# Acoustics_ADC.net
KiCad netlist of a schematic drawn in Altium Designer
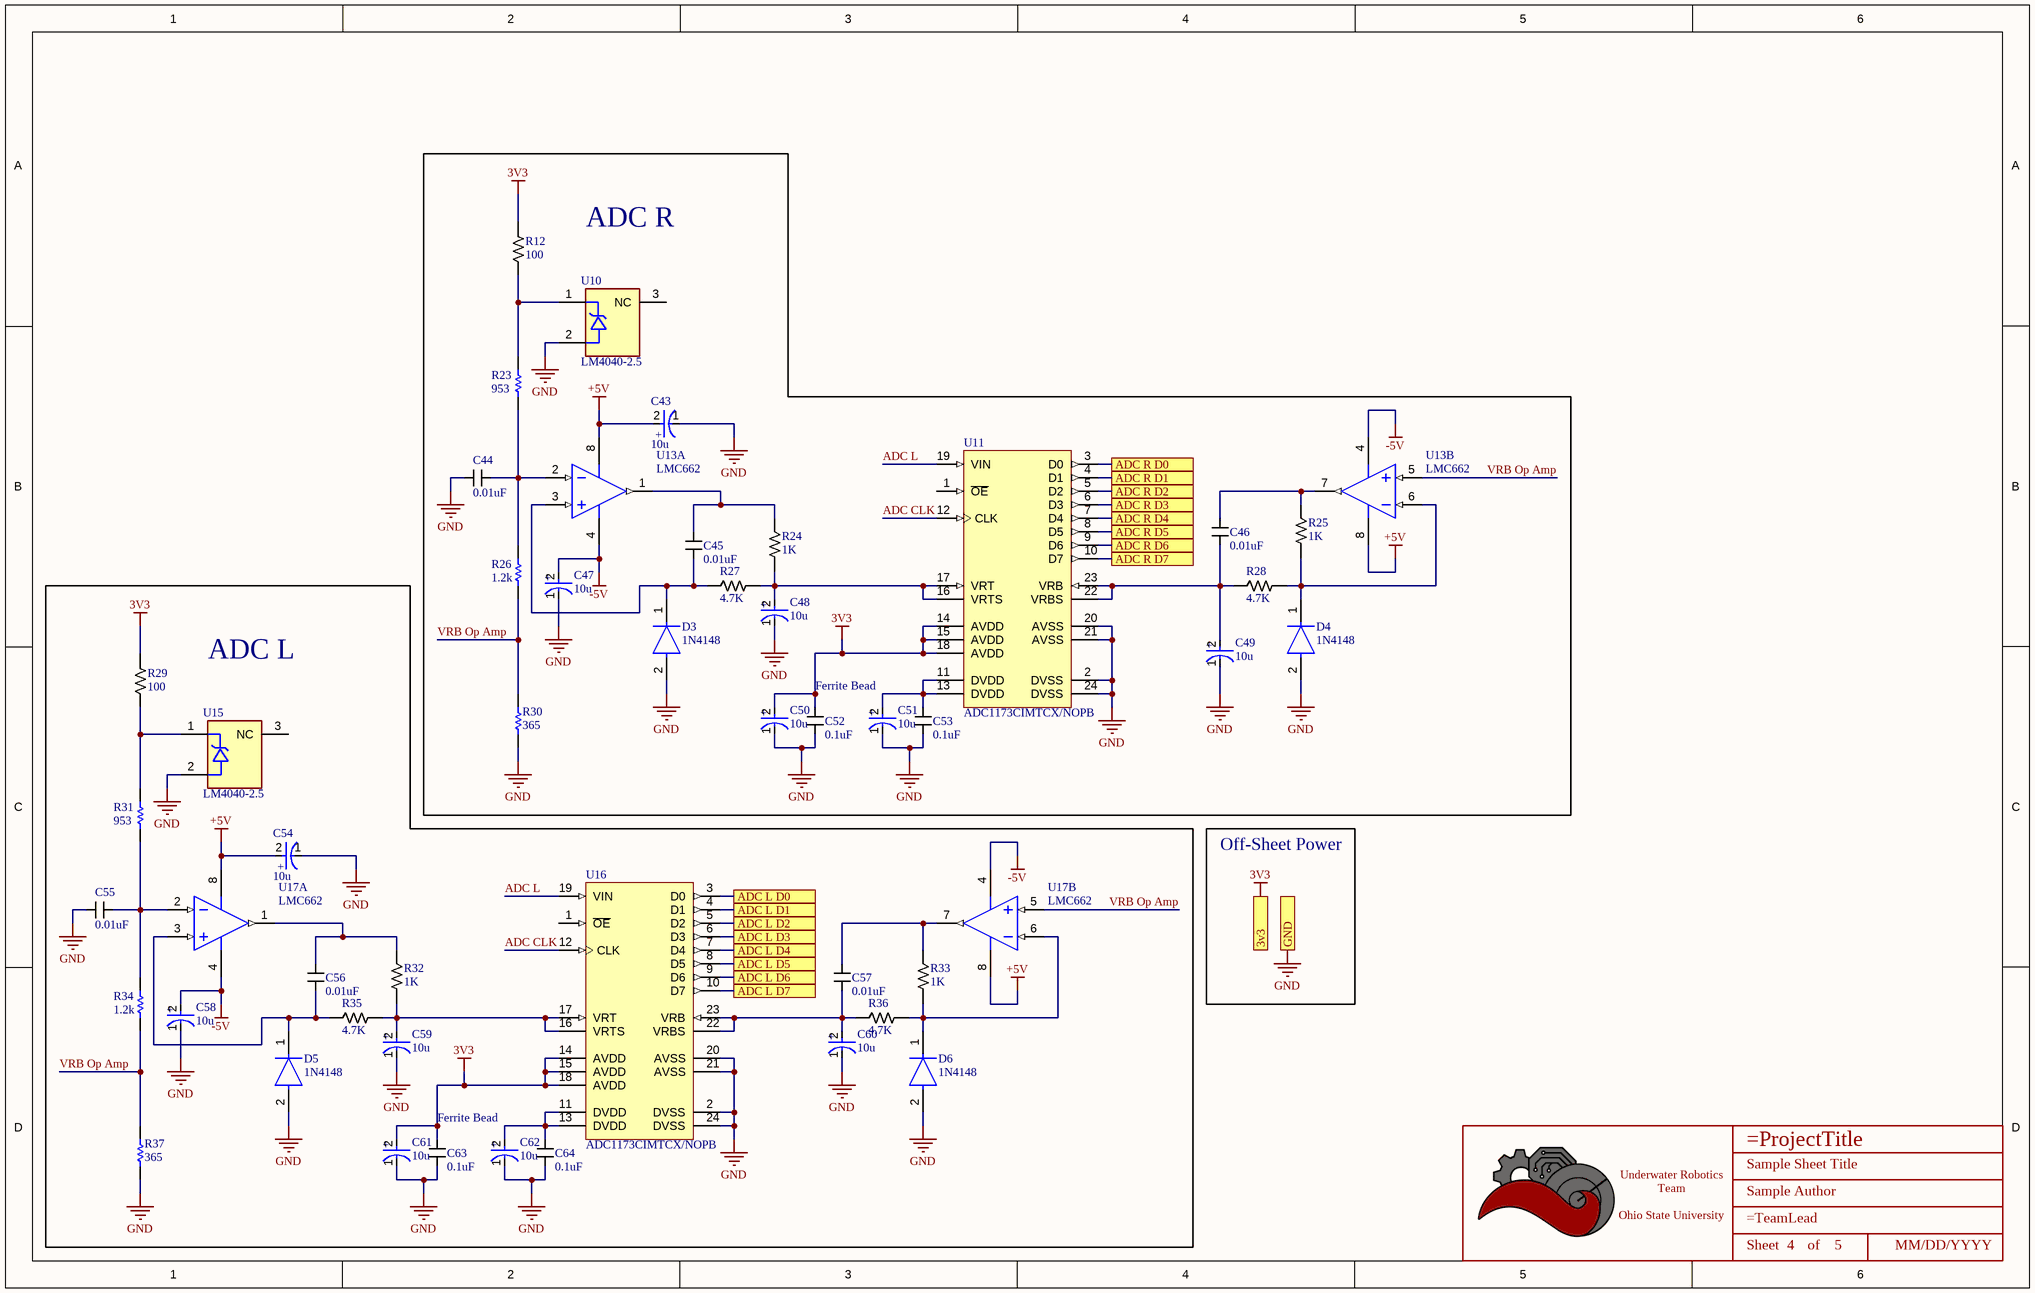
[diagram p0: [Acoustics] ADC.SchDoc]

(export (version "E")
  (design (tool "Eeschema 10.0.6"))
  (components
    (comp (ref "*")
      (value "Title_Block")
      (footprint "LOGO")
      (description "UWRT Schematic Title Block Template\r\n\r\nCreated June 2021, Dylan Trainor")
      (libsource (lib "UWRT") (part "Title_Block"))
    )
    (comp (ref "C43")
      (value "10u")
      (footprint "FP-TCJB-MFG")
      (description "10uF 25V  ±20% 90mΩ 1210  SMD Polymer Capacitor")
      (libsource (lib "Altium Content Vault") (part "a00bbbee19879c290e62620ae7e47b1"))
    )
    (comp (ref "C44")
      (value "0.01uF")
      (footprint "CAPACITOR_0603")
      (description "10000 pF ±10% 50V Ceramic Capacitor X7R 0603 (1608 Metric)")
      (fields
        (field (name "TOLERANCE") "+/- 10%")
        (field (name "VOLTAGE") "6.3V")
        (field (name "MADE BY") "Flip B")
      )
      (libsource (lib "Capacitors") (part "CAPACITOR_0.01uF_0603_50V"))
    )
    (comp (ref "C45")
      (value "0.01uF")
      (footprint "CAPACITOR_0603")
      (description "10000 pF ±10% 50V Ceramic Capacitor X7R 0603 (1608 Metric)")
      (fields
        (field (name "TOLERANCE") "+/- 10%")
        (field (name "VOLTAGE") "6.3V")
        (field (name "MADE BY") "Flip B")
      )
      (libsource (lib "Capacitors") (part "CAPACITOR_0.01uF_0603_50V"))
    )
    (comp (ref "C46")
      (value "0.01uF")
      (footprint "CAPACITOR_0603")
      (description "10000 pF ±10% 50V Ceramic Capacitor X7R 0603 (1608 Metric)")
      (fields
        (field (name "TOLERANCE") "+/- 10%")
        (field (name "VOLTAGE") "6.3V")
        (field (name "MADE BY") "Flip B")
      )
      (libsource (lib "Capacitors") (part "CAPACITOR_0.01uF_0603_50V"))
    )
    (comp (ref "C47")
      (value "10u")
      (footprint "FP-TCJB-MFG")
      (description "10uF 25V  ±20% 90mΩ 1210  SMD Polymer Capacitor")
      (libsource (lib "Altium Content Vault") (part "a00bbbee19879c290e62620ae7e47b1"))
    )
    (comp (ref "C48")
      (value "10u")
      (footprint "FP-TCJB-MFG")
      (description "10uF 25V  ±20% 90mΩ 1210  SMD Polymer Capacitor")
      (libsource (lib "Altium Content Vault") (part "a00bbbee19879c290e62620ae7e47b1"))
    )
    (comp (ref "C49")
      (value "10u")
      (footprint "FP-TCJB-MFG")
      (description "10uF 25V  ±20% 90mΩ 1210  SMD Polymer Capacitor")
      (libsource (lib "Altium Content Vault") (part "a00bbbee19879c290e62620ae7e47b1"))
    )
    (comp (ref "C50")
      (value "10u")
      (footprint "FP-TCJB-MFG")
      (description "10uF 25V  ±20% 90mΩ 1210  SMD Polymer Capacitor")
      (libsource (lib "Altium Content Vault") (part "a00bbbee19879c290e62620ae7e47b1"))
    )
    (comp (ref "C51")
      (value "10u")
      (footprint "FP-TCJB-MFG")
      (description "10uF 25V  ±20% 90mΩ 1210  SMD Polymer Capacitor")
      (libsource (lib "Altium Content Vault") (part "a00bbbee19879c290e62620ae7e47b1"))
    )
    (comp (ref "C52")
      (value "0.1uF")
      (footprint "CAPACITOR_0603")
      (description "Cap 100nF 6.3V +/-10%\r\nCeramic 0603")
      (fields
        (field (name "TOLERANCE") "+/- 10%")
        (field (name "VOLTAGE") "6.3V")
        (field (name "MADE BY") "Flip B")
      )
      (libsource (lib "Capacitors") (part "CAPACITOR_0.1uF_0603"))
    )
    (comp (ref "C53")
      (value "0.1uF")
      (footprint "CAPACITOR_0603")
      (description "Cap 100nF 6.3V +/-10%\r\nCeramic 0603")
      (fields
        (field (name "TOLERANCE") "+/- 10%")
        (field (name "VOLTAGE") "6.3V")
        (field (name "MADE BY") "Flip B")
      )
      (libsource (lib "Capacitors") (part "CAPACITOR_0.1uF_0603"))
    )
    (comp (ref "C54")
      (value "10u")
      (footprint "FP-TCJB-MFG")
      (description "10uF 25V  ±20% 90mΩ 1210  SMD Polymer Capacitor")
      (libsource (lib "Altium Content Vault") (part "a00bbbee19879c290e62620ae7e47b1"))
    )
    (comp (ref "C55")
      (value "0.01uF")
      (footprint "CAPACITOR_0603")
      (description "10000 pF ±10% 50V Ceramic Capacitor X7R 0603 (1608 Metric)")
      (fields
        (field (name "TOLERANCE") "+/- 10%")
        (field (name "VOLTAGE") "6.3V")
        (field (name "MADE BY") "Flip B")
      )
      (libsource (lib "Capacitors") (part "CAPACITOR_0.01uF_0603_50V"))
    )
    (comp (ref "C56")
      (value "0.01uF")
      (footprint "CAPACITOR_0603")
      (description "10000 pF ±10% 50V Ceramic Capacitor X7R 0603 (1608 Metric)")
      (fields
        (field (name "TOLERANCE") "+/- 10%")
        (field (name "VOLTAGE") "6.3V")
        (field (name "MADE BY") "Flip B")
      )
      (libsource (lib "Capacitors") (part "CAPACITOR_0.01uF_0603_50V"))
    )
    (comp (ref "C57")
      (value "0.01uF")
      (footprint "CAPACITOR_0603")
      (description "10000 pF ±10% 50V Ceramic Capacitor X7R 0603 (1608 Metric)")
      (fields
        (field (name "TOLERANCE") "+/- 10%")
        (field (name "VOLTAGE") "6.3V")
        (field (name "MADE BY") "Flip B")
      )
      (libsource (lib "Capacitors") (part "CAPACITOR_0.01uF_0603_50V"))
    )
    (comp (ref "C58")
      (value "10u")
      (footprint "FP-TCJB-MFG")
      (description "10uF 25V  ±20% 90mΩ 1210  SMD Polymer Capacitor")
      (libsource (lib "Altium Content Vault") (part "a00bbbee19879c290e62620ae7e47b1"))
    )
    (comp (ref "C59")
      (value "10u")
      (footprint "FP-TCJB-MFG")
      (description "10uF 25V  ±20% 90mΩ 1210  SMD Polymer Capacitor")
      (libsource (lib "Altium Content Vault") (part "a00bbbee19879c290e62620ae7e47b1"))
    )
    (comp (ref "C60")
      (value "10u")
      (footprint "FP-TCJB-MFG")
      (description "10uF 25V  ±20% 90mΩ 1210  SMD Polymer Capacitor")
      (libsource (lib "Altium Content Vault") (part "a00bbbee19879c290e62620ae7e47b1"))
    )
    (comp (ref "C61")
      (value "10u")
      (footprint "FP-TCJB-MFG")
      (description "10uF 25V  ±20% 90mΩ 1210  SMD Polymer Capacitor")
      (libsource (lib "Altium Content Vault") (part "a00bbbee19879c290e62620ae7e47b1"))
    )
    (comp (ref "C62")
      (value "10u")
      (footprint "FP-TCJB-MFG")
      (description "10uF 25V  ±20% 90mΩ 1210  SMD Polymer Capacitor")
      (libsource (lib "Altium Content Vault") (part "a00bbbee19879c290e62620ae7e47b1"))
    )
    (comp (ref "C63")
      (value "0.1uF")
      (footprint "CAPACITOR_0603")
      (description "Cap 100nF 6.3V +/-10%\r\nCeramic 0603")
      (fields
        (field (name "TOLERANCE") "+/- 10%")
        (field (name "VOLTAGE") "6.3V")
        (field (name "MADE BY") "Flip B")
      )
      (libsource (lib "Capacitors") (part "CAPACITOR_0.1uF_0603"))
    )
    (comp (ref "C64")
      (value "0.1uF")
      (footprint "CAPACITOR_0603")
      (description "Cap 100nF 6.3V +/-10%\r\nCeramic 0603")
      (fields
        (field (name "TOLERANCE") "+/- 10%")
        (field (name "VOLTAGE") "6.3V")
        (field (name "MADE BY") "Flip B")
      )
      (libsource (lib "Capacitors") (part "CAPACITOR_0.1uF_0603"))
    )
    (comp (ref "D3")
      (value "1N4148")
      (footprint "FP-017AG-MFG")
      (description "DIODE GEN PURP 100V 200MA DO35")
      (fields (field (name "VOLTAGE") "100V"))
      (libsource (lib "Altium Content Vault") (part "d7152d700b627762746794eb795d46e"))
    )
    (comp (ref "D4")
      (value "1N4148")
      (footprint "FP-017AG-MFG")
      (description "DIODE GEN PURP 100V 200MA DO35")
      (fields (field (name "VOLTAGE") "100V"))
      (libsource (lib "Altium Content Vault") (part "d7152d700b627762746794eb795d46e"))
    )
    (comp (ref "D5")
      (value "1N4148")
      (footprint "FP-017AG-MFG")
      (description "DIODE GEN PURP 100V 200MA DO35")
      (fields (field (name "VOLTAGE") "100V"))
      (libsource (lib "Altium Content Vault") (part "d7152d700b627762746794eb795d46e"))
    )
    (comp (ref "D6")
      (value "1N4148")
      (footprint "FP-017AG-MFG")
      (description "DIODE GEN PURP 100V 200MA DO35")
      (fields (field (name "VOLTAGE") "100V"))
      (libsource (lib "Altium Content Vault") (part "d7152d700b627762746794eb795d46e"))
    )
    (comp (ref "R12")
      (value "100 Ohm 5% 1/16W")
      (footprint "RESISTOR_0402")
      (description "RES 100 OHM 5% 1/16W 0402")
      (fields
        (field (name "TOLERANCE") "+/- 5%")
        (field (name "VALUE  (OHMS)") "100")
        (field (name "MADE BY") "Flip B")
      )
      (libsource (lib "Resistors") (part "RESISTOR_100_0402"))
    )
    (comp (ref "R23")
      (value "953")
      (footprint "RESC1005X40X25ML05T05")
      (fields (field (name "PART NUMBER") "ERJ-2RKF9530X") (field (name "MANUFACTURER") "Panasonic"))
      (libsource (lib "Altium Content Vault") (part "RES"))
    )
    (comp (ref "R24")
      (value "1k Ohm 1% 1/16W")
      (footprint "RESISTOR_0402")
      (description "RES 1k OHM 1% 1/16W 0402")
      (fields
        (field (name "TOLERANCE") "+/- 1%")
        (field (name "VALUE  (OHMS)") "1K")
        (field (name "MADE BY") "Robert Pafford")
      )
      (libsource (lib "Resistors") (part "RESISTOR_1K_0402"))
    )
    (comp (ref "R25")
      (value "1k Ohm 1% 1/16W")
      (footprint "RESISTOR_0402")
      (description "RES 1k OHM 1% 1/16W 0402")
      (fields
        (field (name "TOLERANCE") "+/- 1%")
        (field (name "VALUE  (OHMS)") "1K")
        (field (name "MADE BY") "Robert Pafford")
      )
      (libsource (lib "Resistors") (part "RESISTOR_1K_0402"))
    )
    (comp (ref "R26")
      (value "1.2k")
      (footprint "RESC1005X40X25NL05T10")
      (fields (field (name "PART NUMBER") "RC0402JR-071K2L") (field (name "MANUFACTURER") "Yageo / Phycomp"))
      (libsource (lib "Altium Content Vault") (part "RES"))
    )
    (comp (ref "R27")
      (value "4.7k Ohm 1% 1/16W")
      (footprint "RESISTOR_0402")
      (description "RES 4.7k OHM 1% 1/16W 0402")
      (fields
        (field (name "TOLERANCE") "+/- 1%")
        (field (name "VALUE  (OHMS)") "4.7K")
        (field (name "MADE BY") "Robert Pafford")
      )
      (libsource (lib "Resistors") (part "RESISTOR_4.7K_0402"))
    )
    (comp (ref "R28")
      (value "4.7k Ohm 1% 1/16W")
      (footprint "RESISTOR_0402")
      (description "RES 4.7k OHM 1% 1/16W 0402")
      (fields
        (field (name "TOLERANCE") "+/- 1%")
        (field (name "VALUE  (OHMS)") "4.7K")
        (field (name "MADE BY") "Robert Pafford")
      )
      (libsource (lib "Resistors") (part "RESISTOR_4.7K_0402"))
    )
    (comp (ref "R29")
      (value "100 Ohm 5% 1/16W")
      (footprint "RESISTOR_0402")
      (description "RES 100 OHM 5% 1/16W 0402")
      (fields
        (field (name "TOLERANCE") "+/- 5%")
        (field (name "VALUE  (OHMS)") "100")
        (field (name "MADE BY") "Flip B")
      )
      (libsource (lib "Resistors") (part "RESISTOR_100_0402"))
    )
    (comp (ref "R30")
      (value "365")
      (footprint "RESC1005X40X25ML05T05")
      (fields (field (name "PART NUMBER") "ERJ-2RKF3650X") (field (name "MANUFACTURER") "Panasonic"))
      (libsource (lib "Altium Content Vault") (part "RES"))
    )
    (comp (ref "R31")
      (value "953")
      (footprint "RESC1005X40X25ML05T05")
      (fields (field (name "PART NUMBER") "ERJ-2RKF9530X") (field (name "MANUFACTURER") "Panasonic"))
      (libsource (lib "Altium Content Vault") (part "RES"))
    )
    (comp (ref "R32")
      (value "1k Ohm 1% 1/16W")
      (footprint "RESISTOR_0402")
      (description "RES 1k OHM 1% 1/16W 0402")
      (fields
        (field (name "TOLERANCE") "+/- 1%")
        (field (name "VALUE  (OHMS)") "1K")
        (field (name "MADE BY") "Robert Pafford")
      )
      (libsource (lib "Resistors") (part "RESISTOR_1K_0402"))
    )
    (comp (ref "R33")
      (value "1k Ohm 1% 1/16W")
      (footprint "RESISTOR_0402")
      (description "RES 1k OHM 1% 1/16W 0402")
      (fields
        (field (name "TOLERANCE") "+/- 1%")
        (field (name "VALUE  (OHMS)") "1K")
        (field (name "MADE BY") "Robert Pafford")
      )
      (libsource (lib "Resistors") (part "RESISTOR_1K_0402"))
    )
    (comp (ref "R34")
      (value "1.2k")
      (footprint "RESC1005X40X25NL05T10")
      (fields (field (name "PART NUMBER") "RC0402JR-071K2L") (field (name "MANUFACTURER") "Yageo / Phycomp"))
      (libsource (lib "Altium Content Vault") (part "RES"))
    )
    (comp (ref "R35")
      (value "4.7k Ohm 1% 1/16W")
      (footprint "RESISTOR_0402")
      (description "RES 4.7k OHM 1% 1/16W 0402")
      (fields
        (field (name "TOLERANCE") "+/- 1%")
        (field (name "VALUE  (OHMS)") "4.7K")
        (field (name "MADE BY") "Robert Pafford")
      )
      (libsource (lib "Resistors") (part "RESISTOR_4.7K_0402"))
    )
    (comp (ref "R36")
      (value "4.7k Ohm 1% 1/16W")
      (footprint "RESISTOR_0402")
      (description "RES 4.7k OHM 1% 1/16W 0402")
      (fields
        (field (name "TOLERANCE") "+/- 1%")
        (field (name "VALUE  (OHMS)") "4.7K")
        (field (name "MADE BY") "Robert Pafford")
      )
      (libsource (lib "Resistors") (part "RESISTOR_4.7K_0402"))
    )
    (comp (ref "R37")
      (value "365")
      (footprint "RESC1005X40X25ML05T05")
      (fields (field (name "PART NUMBER") "ERJ-2RKF3650X") (field (name "MANUFACTURER") "Panasonic"))
      (libsource (lib "Altium Content Vault") (part "RES"))
    )
    (comp (ref "U10")
      (value "LM4040-2.5")
      (footprint "FP-SOT23-3LD-PL-1-MFG")
      (description "IC VREF SHUNT 2.5V SOT23-3")
      (fields
        (field (name "MANUFACTURER") "Microchip")
        (field (name "MANUFACTURER PART NUMBER") "LM4040CYM3-2.5-TR")
      )
      (libsource (lib "Altium Content Vault") (part "e08089692d8b94833b83a492544ec0b"))
    )
    (comp (ref "U11")
      (value "ADC1173CIMTCX/NOPB")
      (footprint "PW0024A_L")
      (description "8-Bit, 3-Volt, 15MSPS, 33mW A/D Converter, 24-pin TSSOP, Pb-Free")
      (fields (field (name "MANUFACTURER") "Texas Instruments"))
      (libsource (lib "Altium Content Vault") (part "CON-ADC-ADC1175CIMTC"))
    )
    (comp (ref "U13")
      (value "LMC662")
      (footprint "D0008A_L")
      (description "CMOS Dual Operational Amplifier, 8-pin Narrow SOIC, Pb-Free")
      (fields (field (name "MANUFACTURER") "Texas Instruments"))
      (libsource (lib "Altium Content Vault") (part "AMP-OPA-LF353-8"))
    )
    (comp (ref "U15")
      (value "LM4040-2.5")
      (footprint "FP-SOT23-3LD-PL-1-MFG")
      (description "IC VREF SHUNT 2.5V SOT23-3")
      (fields
        (field (name "MANUFACTURER") "Microchip")
        (field (name "MANUFACTURER PART NUMBER") "LM4040CYM3-2.5-TR")
      )
      (libsource (lib "Altium Content Vault") (part "e08089692d8b94833b83a492544ec0b"))
    )
    (comp (ref "U16")
      (value "ADC1173CIMTCX/NOPB")
      (footprint "PW0024A_L")
      (description "8-Bit, 3-Volt, 15MSPS, 33mW A/D Converter, 24-pin TSSOP, Pb-Free")
      (fields (field (name "MANUFACTURER") "Texas Instruments"))
      (libsource (lib "Altium Content Vault") (part "CON-ADC-ADC1175CIMTC"))
    )
    (comp (ref "U17")
      (value "LMC662")
      (footprint "D0008A_L")
      (description "CMOS Dual Operational Amplifier, 8-pin Narrow SOIC, Pb-Free")
      (fields (field (name "MANUFACTURER") "Texas Instruments"))
      (libsource (lib "Altium Content Vault") (part "AMP-OPA-LF353-8"))
    )
  )
  (nets
    (net (code "1") (name "+5V") (class "Default")
      (node (ref "C43") (pin "2") (pinfunction "A_2") (pintype "passive"))
      (node (ref "C54") (pin "2") (pinfunction "A_2") (pintype "passive"))
      (node (ref "U13") (pin "8") (pinfunction "V+_8") (pintype "power_in"))
      (node (ref "U17") (pin "8") (pinfunction "V+_8") (pintype "power_in"))
    )
    (net (code "2") (name "-5V") (class "Default")
      (node (ref "C47") (pin "2") (pinfunction "A_2") (pintype "passive"))
      (node (ref "C58") (pin "2") (pinfunction "A_2") (pintype "passive"))
      (node (ref "U13") (pin "4") (pinfunction "V-_4") (pintype "power_in"))
      (node (ref "U17") (pin "4") (pinfunction "V-_4") (pintype "power_in"))
    )
    (net (code "3") (name "/ADC CLK") (class "Default")
      (node (ref "U11") (pin "12") (pinfunction "CLK_12") (pintype "input"))
      (node (ref "U16") (pin "12") (pinfunction "CLK_12") (pintype "input"))
    )
    (net (code "4") (name "/ADC L") (class "Default")
      (node (ref "U11") (pin "19") (pinfunction "VIN_19") (pintype "input"))
      (node (ref "U16") (pin "19") (pinfunction "VIN_19") (pintype "input"))
    )
    (net (code "5") (name "/ADC L D0") (class "Default")
      (node (ref "U16") (pin "3") (pinfunction "D0_3") (pintype "output"))
    )
    (net (code "6") (name "/ADC L D1") (class "Default")
      (node (ref "U16") (pin "4") (pinfunction "D1_4") (pintype "output"))
    )
    (net (code "7") (name "/ADC L D2") (class "Default")
      (node (ref "U16") (pin "5") (pinfunction "D2_5") (pintype "output"))
    )
    (net (code "8") (name "/ADC L D3") (class "Default")
      (node (ref "U16") (pin "6") (pinfunction "D3_6") (pintype "output"))
    )
    (net (code "9") (name "/ADC L D4") (class "Default")
      (node (ref "U16") (pin "7") (pinfunction "D4_7") (pintype "output"))
    )
    (net (code "10") (name "/ADC L D5") (class "Default")
      (node (ref "U16") (pin "8") (pinfunction "D5_8") (pintype "output"))
    )
    (net (code "11") (name "/ADC L D6") (class "Default")
      (node (ref "U16") (pin "9") (pinfunction "D6_9") (pintype "output"))
    )
    (net (code "12") (name "/ADC L D7") (class "Default")
      (node (ref "U16") (pin "10") (pinfunction "D7_10") (pintype "output"))
    )
    (net (code "13") (name "/ADC R D0") (class "Default")
      (node (ref "U11") (pin "3") (pinfunction "D0_3") (pintype "output"))
    )
    (net (code "14") (name "/ADC R D1") (class "Default")
      (node (ref "U11") (pin "4") (pinfunction "D1_4") (pintype "output"))
    )
    (net (code "15") (name "/ADC R D2") (class "Default")
      (node (ref "U11") (pin "5") (pinfunction "D2_5") (pintype "output"))
    )
    (net (code "16") (name "/ADC R D3") (class "Default")
      (node (ref "U11") (pin "6") (pinfunction "D3_6") (pintype "output"))
    )
    (net (code "17") (name "/ADC R D4") (class "Default")
      (node (ref "U11") (pin "7") (pinfunction "D4_7") (pintype "output"))
    )
    (net (code "18") (name "/ADC R D5") (class "Default")
      (node (ref "U11") (pin "8") (pinfunction "D5_8") (pintype "output"))
    )
    (net (code "19") (name "/ADC R D6") (class "Default")
      (node (ref "U11") (pin "9") (pinfunction "D6_9") (pintype "output"))
    )
    (net (code "20") (name "/ADC R D7") (class "Default")
      (node (ref "U11") (pin "10") (pinfunction "D7_10") (pintype "output"))
    )
    (net (code "21") (name "/VRB Op Amp") (class "Default")
      (node (ref "R26") (pin "1") (pinfunction "1_1") (pintype "passive"))
      (node (ref "R30") (pin "2") (pinfunction "2_2") (pintype "passive"))
      (node (ref "R34") (pin "1") (pinfunction "1_1") (pintype "passive"))
      (node (ref "R37") (pin "2") (pinfunction "2_2") (pintype "passive"))
      (node (ref "U13") (pin "5") (pinfunction "INB+_5") (pintype "input"))
      (node (ref "U17") (pin "5") (pinfunction "INB+_5") (pintype "input"))
    )
    (net (code "22") (name "3V3") (class "Default")
      (node (ref "C50") (pin "2") (pinfunction "A_2") (pintype "passive"))
      (node (ref "C52") (pin "1") (pinfunction "1_1") (pintype "passive"))
      (node (ref "C61") (pin "2") (pinfunction "A_2") (pintype "passive"))
      (node (ref "C63") (pin "1") (pinfunction "1_1") (pintype "passive"))
      (node (ref "R12") (pin "1") (pinfunction "1_1") (pintype "passive"))
      (node (ref "R29") (pin "1") (pinfunction "1_1") (pintype "passive"))
      (node (ref "U11") (pin "14") (pinfunction "AVDD_14") (pintype "power_in"))
      (node (ref "U11") (pin "15") (pinfunction "AVDD_15") (pintype "power_in"))
      (node (ref "U11") (pin "18") (pinfunction "AVDD_18") (pintype "power_in"))
      (node (ref "U16") (pin "14") (pinfunction "AVDD_14") (pintype "power_in"))
      (node (ref "U16") (pin "15") (pinfunction "AVDD_15") (pintype "power_in"))
      (node (ref "U16") (pin "18") (pinfunction "AVDD_18") (pintype "power_in"))
    )
    (net (code "23") (name "GND") (class "Default")
      (node (ref "C43") (pin "1") (pinfunction "C_1") (pintype "passive"))
      (node (ref "C44") (pin "2") (pinfunction "2_2") (pintype "passive"))
      (node (ref "C47") (pin "1") (pinfunction "C_1") (pintype "passive"))
      (node (ref "C48") (pin "1") (pinfunction "C_1") (pintype "passive"))
      (node (ref "C49") (pin "1") (pinfunction "C_1") (pintype "passive"))
      (node (ref "C50") (pin "1") (pinfunction "C_1") (pintype "passive"))
      (node (ref "C51") (pin "1") (pinfunction "C_1") (pintype "passive"))
      (node (ref "C52") (pin "2") (pinfunction "2_2") (pintype "passive"))
      (node (ref "C53") (pin "2") (pinfunction "2_2") (pintype "passive"))
      (node (ref "C54") (pin "1") (pinfunction "C_1") (pintype "passive"))
      (node (ref "C55") (pin "2") (pinfunction "2_2") (pintype "passive"))
      (node (ref "C58") (pin "1") (pinfunction "C_1") (pintype "passive"))
      (node (ref "C59") (pin "1") (pinfunction "C_1") (pintype "passive"))
      (node (ref "C60") (pin "1") (pinfunction "C_1") (pintype "passive"))
      (node (ref "C61") (pin "1") (pinfunction "C_1") (pintype "passive"))
      (node (ref "C62") (pin "1") (pinfunction "C_1") (pintype "passive"))
      (node (ref "C63") (pin "2") (pinfunction "2_2") (pintype "passive"))
      (node (ref "C64") (pin "2") (pinfunction "2_2") (pintype "passive"))
      (node (ref "D3") (pin "2") (pinfunction "A_2") (pintype "passive"))
      (node (ref "D4") (pin "2") (pinfunction "A_2") (pintype "passive"))
      (node (ref "D5") (pin "2") (pinfunction "A_2") (pintype "passive"))
      (node (ref "D6") (pin "2") (pinfunction "A_2") (pintype "passive"))
      (node (ref "R30") (pin "1") (pinfunction "1_1") (pintype "passive"))
      (node (ref "R37") (pin "1") (pinfunction "1_1") (pintype "passive"))
      (node (ref "U10") (pin "2") (pinfunction "-_2") (pintype "passive"))
      (node (ref "U11") (pin "2") (pinfunction "DVSS_2") (pintype "power_in"))
      (node (ref "U11") (pin "20") (pinfunction "AVSS_20") (pintype "power_in"))
      (node (ref "U11") (pin "21") (pinfunction "AVSS_21") (pintype "power_in"))
      (node (ref "U11") (pin "24") (pinfunction "DVSS_24") (pintype "power_in"))
      (node (ref "U15") (pin "2") (pinfunction "-_2") (pintype "passive"))
      (node (ref "U16") (pin "2") (pinfunction "DVSS_2") (pintype "power_in"))
      (node (ref "U16") (pin "20") (pinfunction "AVSS_20") (pintype "power_in"))
      (node (ref "U16") (pin "21") (pinfunction "AVSS_21") (pintype "power_in"))
      (node (ref "U16") (pin "24") (pinfunction "DVSS_24") (pintype "power_in"))
    )
    (net (code "24") (name "Net-(C48-A)") (class "Default")
      (node (ref "C48") (pin "2") (pinfunction "A_2") (pintype "passive"))
      (node (ref "R24") (pin "1") (pinfunction "1_1") (pintype "passive"))
      (node (ref "R27") (pin "1") (pinfunction "1_1") (pintype "passive"))
      (node (ref "U11") (pin "16") (pinfunction "VRTS_16") (pintype "passive"))
      (node (ref "U11") (pin "17") (pinfunction "VRT_17") (pintype "input"))
    )
    (net (code "25") (name "Net-(C49-A)") (class "Default")
      (node (ref "C46") (pin "2") (pinfunction "2_2") (pintype "passive"))
      (node (ref "C49") (pin "2") (pinfunction "A_2") (pintype "passive"))
      (node (ref "R28") (pin "2") (pinfunction "2_2") (pintype "passive"))
      (node (ref "U11") (pin "22") (pinfunction "VRBS_22") (pintype "passive"))
      (node (ref "U11") (pin "23") (pinfunction "VRB_23") (pintype "input"))
    )
    (net (code "26") (name "Net-(C51-A)") (class "Default")
      (node (ref "C51") (pin "2") (pinfunction "A_2") (pintype "passive"))
      (node (ref "C53") (pin "1") (pinfunction "1_1") (pintype "passive"))
      (node (ref "U11") (pin "11") (pinfunction "DVDD_11") (pintype "power_in"))
      (node (ref "U11") (pin "13") (pinfunction "DVDD_13") (pintype "power_in"))
    )
    (net (code "27") (name "Net-(C59-A)") (class "Default")
      (node (ref "C59") (pin "2") (pinfunction "A_2") (pintype "passive"))
      (node (ref "R32") (pin "1") (pinfunction "1_1") (pintype "passive"))
      (node (ref "R35") (pin "1") (pinfunction "1_1") (pintype "passive"))
      (node (ref "U16") (pin "16") (pinfunction "VRTS_16") (pintype "passive"))
      (node (ref "U16") (pin "17") (pinfunction "VRT_17") (pintype "input"))
    )
    (net (code "28") (name "Net-(C60-A)") (class "Default")
      (node (ref "C57") (pin "2") (pinfunction "2_2") (pintype "passive"))
      (node (ref "C60") (pin "2") (pinfunction "A_2") (pintype "passive"))
      (node (ref "R36") (pin "2") (pinfunction "2_2") (pintype "passive"))
      (node (ref "U16") (pin "22") (pinfunction "VRBS_22") (pintype "passive"))
      (node (ref "U16") (pin "23") (pinfunction "VRB_23") (pintype "input"))
    )
    (net (code "29") (name "Net-(C62-A)") (class "Default")
      (node (ref "C62") (pin "2") (pinfunction "A_2") (pintype "passive"))
      (node (ref "C64") (pin "1") (pinfunction "1_1") (pintype "passive"))
      (node (ref "U16") (pin "11") (pinfunction "DVDD_11") (pintype "power_in"))
      (node (ref "U16") (pin "13") (pinfunction "DVDD_13") (pintype "power_in"))
    )
    (net (code "30") (name "Net-(D3-C)") (class "Default")
      (node (ref "C45") (pin "2") (pinfunction "2_2") (pintype "passive"))
      (node (ref "D3") (pin "1") (pinfunction "C_1") (pintype "passive"))
      (node (ref "R27") (pin "2") (pinfunction "2_2") (pintype "passive"))
      (node (ref "U13") (pin "3") (pinfunction "INA+_3") (pintype "input"))
    )
    (net (code "31") (name "Net-(D4-C)") (class "Default")
      (node (ref "D4") (pin "1") (pinfunction "C_1") (pintype "passive"))
      (node (ref "R25") (pin "1") (pinfunction "1_1") (pintype "passive"))
      (node (ref "R28") (pin "1") (pinfunction "1_1") (pintype "passive"))
      (node (ref "U13") (pin "6") (pinfunction "INB-_6") (pintype "input"))
    )
    (net (code "32") (name "Net-(D5-C)") (class "Default")
      (node (ref "C56") (pin "2") (pinfunction "2_2") (pintype "passive"))
      (node (ref "D5") (pin "1") (pinfunction "C_1") (pintype "passive"))
      (node (ref "R35") (pin "2") (pinfunction "2_2") (pintype "passive"))
      (node (ref "U17") (pin "3") (pinfunction "INA+_3") (pintype "input"))
    )
    (net (code "33") (name "Net-(D6-C)") (class "Default")
      (node (ref "D6") (pin "1") (pinfunction "C_1") (pintype "passive"))
      (node (ref "R33") (pin "1") (pinfunction "1_1") (pintype "passive"))
      (node (ref "R36") (pin "1") (pinfunction "1_1") (pintype "passive"))
      (node (ref "U17") (pin "6") (pinfunction "INB-_6") (pintype "input"))
    )
    (net (code "34") (name "Net-(U10-+)") (class "Default")
      (node (ref "R12") (pin "2") (pinfunction "2_2") (pintype "passive"))
      (node (ref "R23") (pin "2") (pinfunction "2_2") (pintype "passive"))
      (node (ref "U10") (pin "1") (pinfunction "+_1") (pintype "passive"))
    )
    (net (code "35") (name "Net-(U13A-INA-)") (class "Default")
      (node (ref "C44") (pin "1") (pinfunction "1_1") (pintype "passive"))
      (node (ref "R23") (pin "1") (pinfunction "1_1") (pintype "passive"))
      (node (ref "R26") (pin "2") (pinfunction "2_2") (pintype "passive"))
      (node (ref "U13") (pin "2") (pinfunction "INA-_2") (pintype "input"))
    )
    (net (code "36") (name "Net-(U13A-OUTA)") (class "Default")
      (node (ref "C45") (pin "1") (pinfunction "1_1") (pintype "passive"))
      (node (ref "R24") (pin "2") (pinfunction "2_2") (pintype "passive"))
      (node (ref "U13") (pin "1") (pinfunction "OUTA_1") (pintype "output"))
    )
    (net (code "37") (name "Net-(U13B-OUTB)") (class "Default")
      (node (ref "C46") (pin "1") (pinfunction "1_1") (pintype "passive"))
      (node (ref "R25") (pin "2") (pinfunction "2_2") (pintype "passive"))
      (node (ref "U13") (pin "7") (pinfunction "OUTB_7") (pintype "output"))
    )
    (net (code "38") (name "Net-(U15-+)") (class "Default")
      (node (ref "R29") (pin "2") (pinfunction "2_2") (pintype "passive"))
      (node (ref "R31") (pin "2") (pinfunction "2_2") (pintype "passive"))
      (node (ref "U15") (pin "1") (pinfunction "+_1") (pintype "passive"))
    )
    (net (code "39") (name "Net-(U17A-INA-)") (class "Default")
      (node (ref "C55") (pin "1") (pinfunction "1_1") (pintype "passive"))
      (node (ref "R31") (pin "1") (pinfunction "1_1") (pintype "passive"))
      (node (ref "R34") (pin "2") (pinfunction "2_2") (pintype "passive"))
      (node (ref "U17") (pin "2") (pinfunction "INA-_2") (pintype "input"))
    )
    (net (code "40") (name "Net-(U17A-OUTA)") (class "Default")
      (node (ref "C56") (pin "1") (pinfunction "1_1") (pintype "passive"))
      (node (ref "R32") (pin "2") (pinfunction "2_2") (pintype "passive"))
      (node (ref "U17") (pin "1") (pinfunction "OUTA_1") (pintype "output"))
    )
    (net (code "41") (name "Net-(U17B-OUTB)") (class "Default")
      (node (ref "C57") (pin "1") (pinfunction "1_1") (pintype "passive"))
      (node (ref "R33") (pin "2") (pinfunction "2_2") (pintype "passive"))
      (node (ref "U17") (pin "7") (pinfunction "OUTB_7") (pintype "output"))
    )
    (net (code "42") (name "unconnected-(U10-NC-Pad3)") (class "Default")
      (node (ref "U10") (pin "3") (pinfunction "NC_3") (pintype "passive"))
    )
    (net (code "43") (name "unconnected-(U11-~{OE}-Pad1)") (class "Default")
      (node (ref "U11") (pin "1") (pinfunction "~{OE}_1") (pintype "input"))
    )
    (net (code "44") (name "unconnected-(U15-NC-Pad3)") (class "Default")
      (node (ref "U15") (pin "3") (pinfunction "NC_3") (pintype "passive"))
    )
    (net (code "45") (name "unconnected-(U16-~{OE}-Pad1)") (class "Default")
      (node (ref "U16") (pin "1") (pinfunction "~{OE}_1") (pintype "input"))
    )
  )
)
